# motor_module.net
KiCad netlist of a schematic drawn in EAGLE
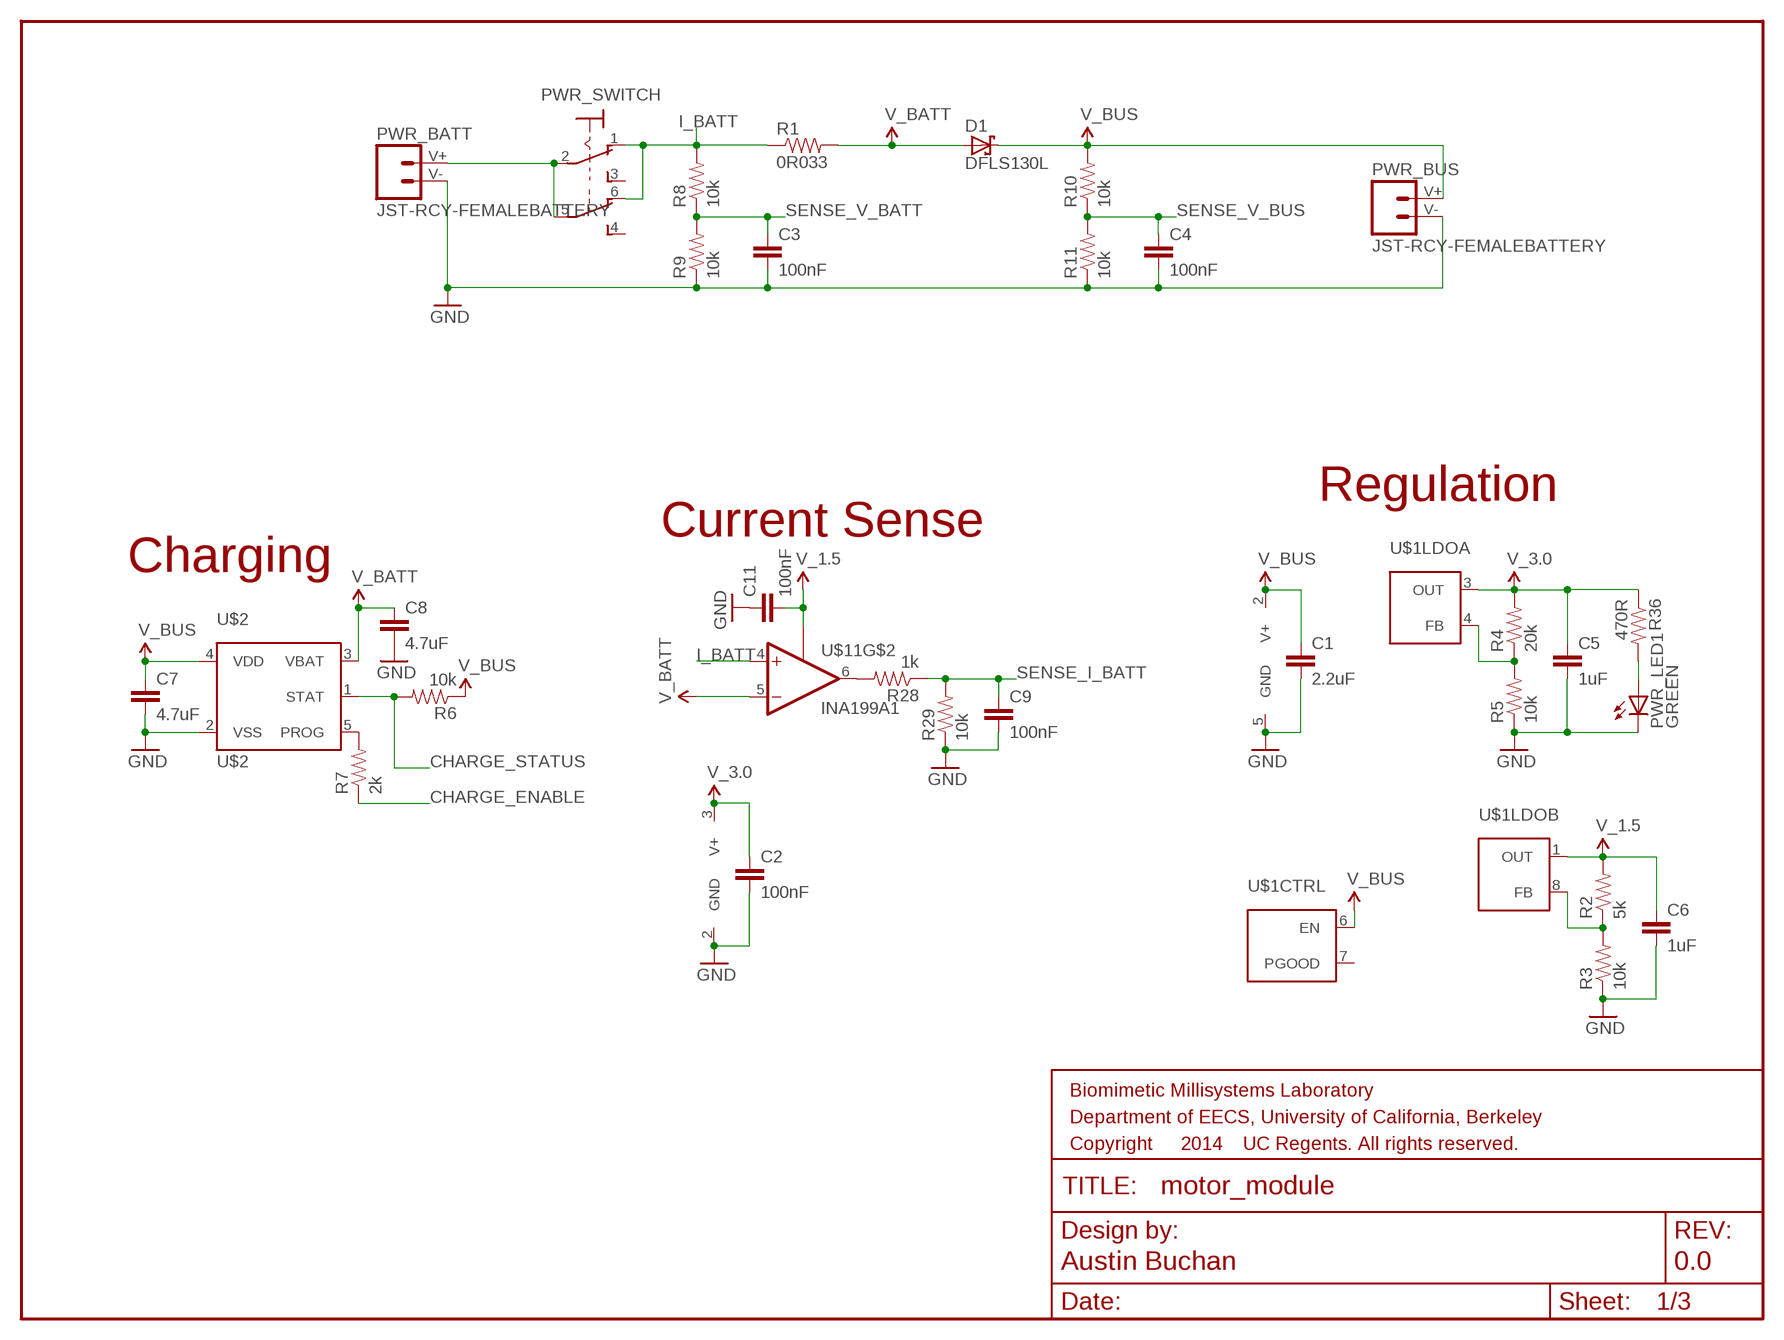
[diagram p0: schematic, sheet 1]
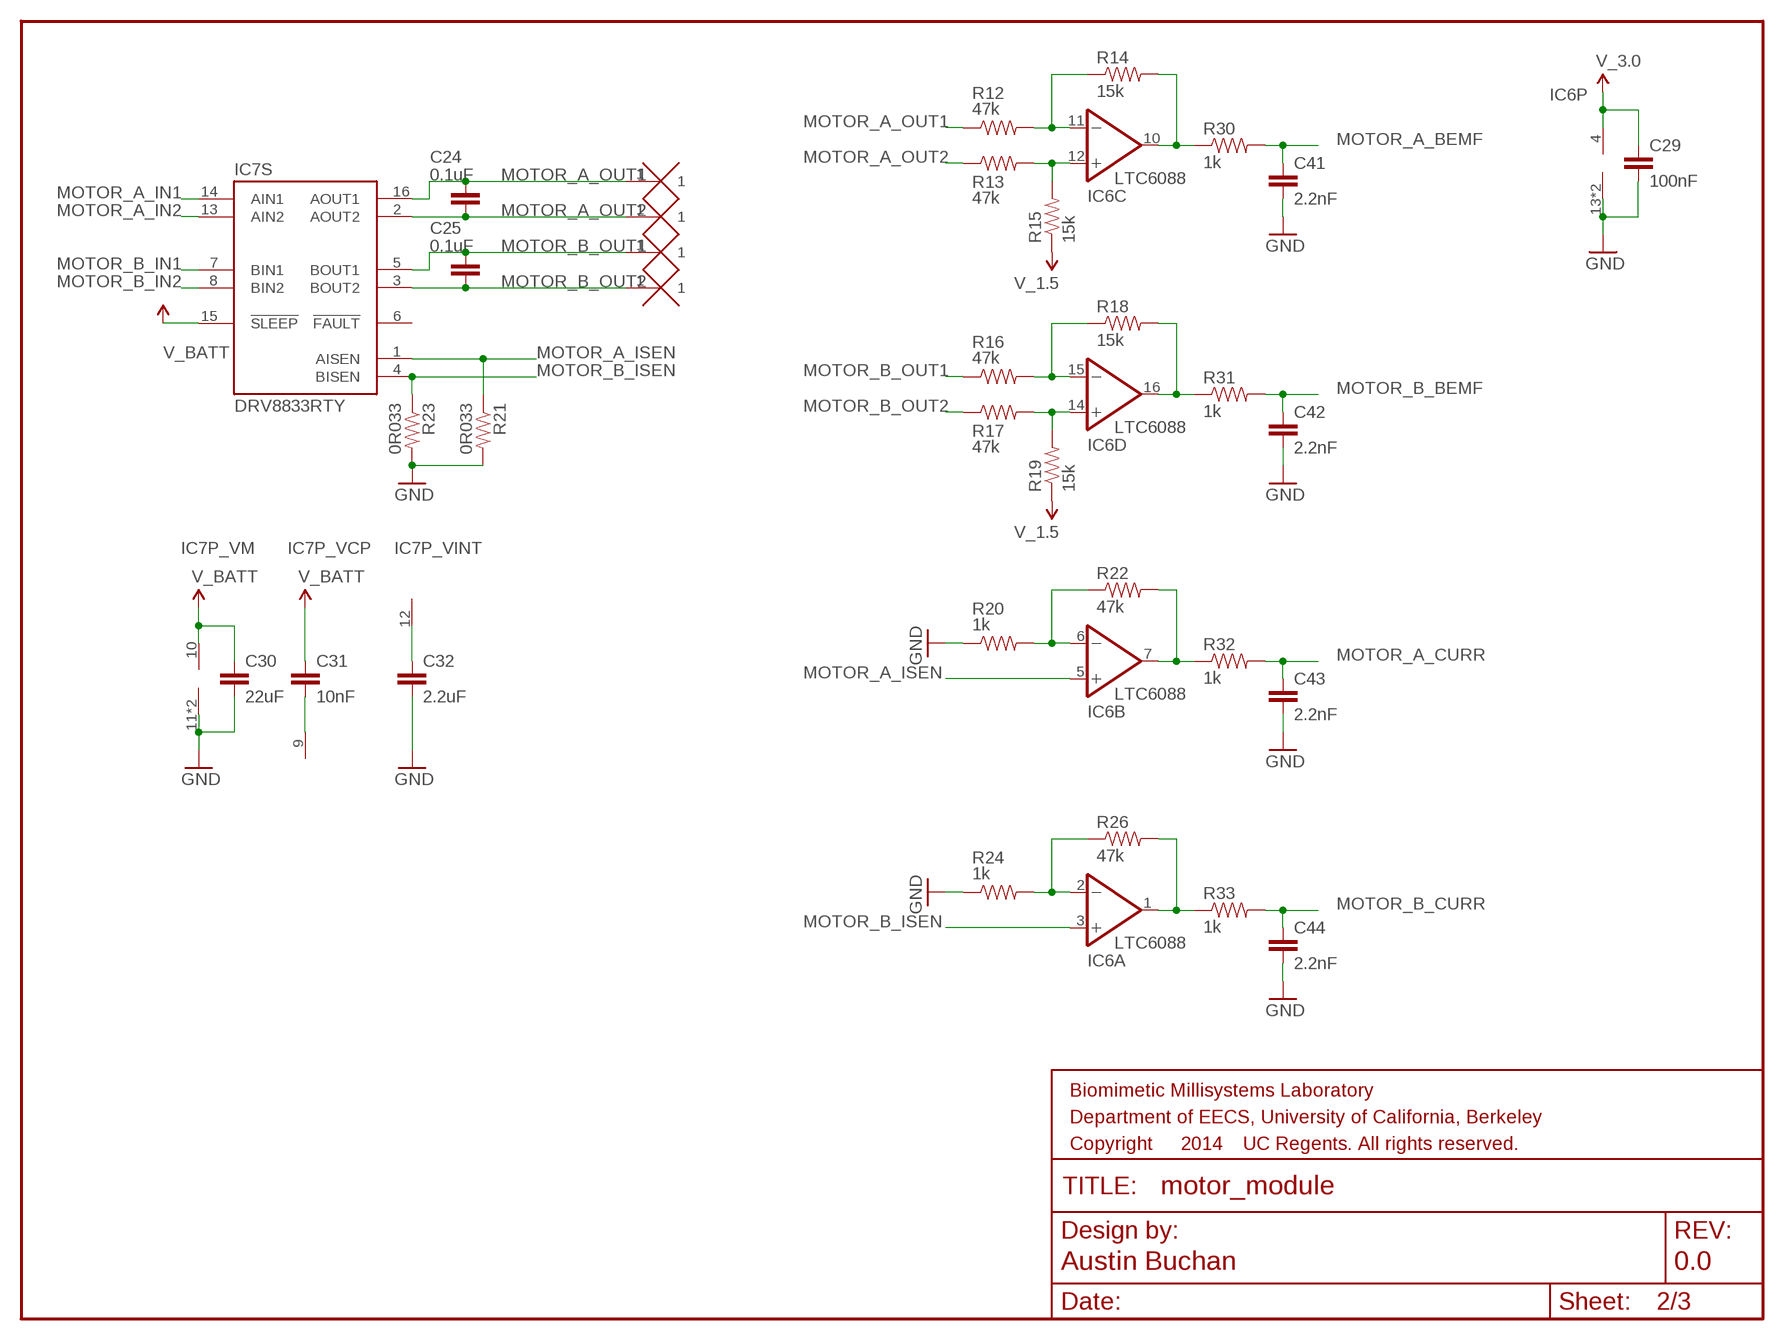
[diagram p1: schematic, sheet 2]
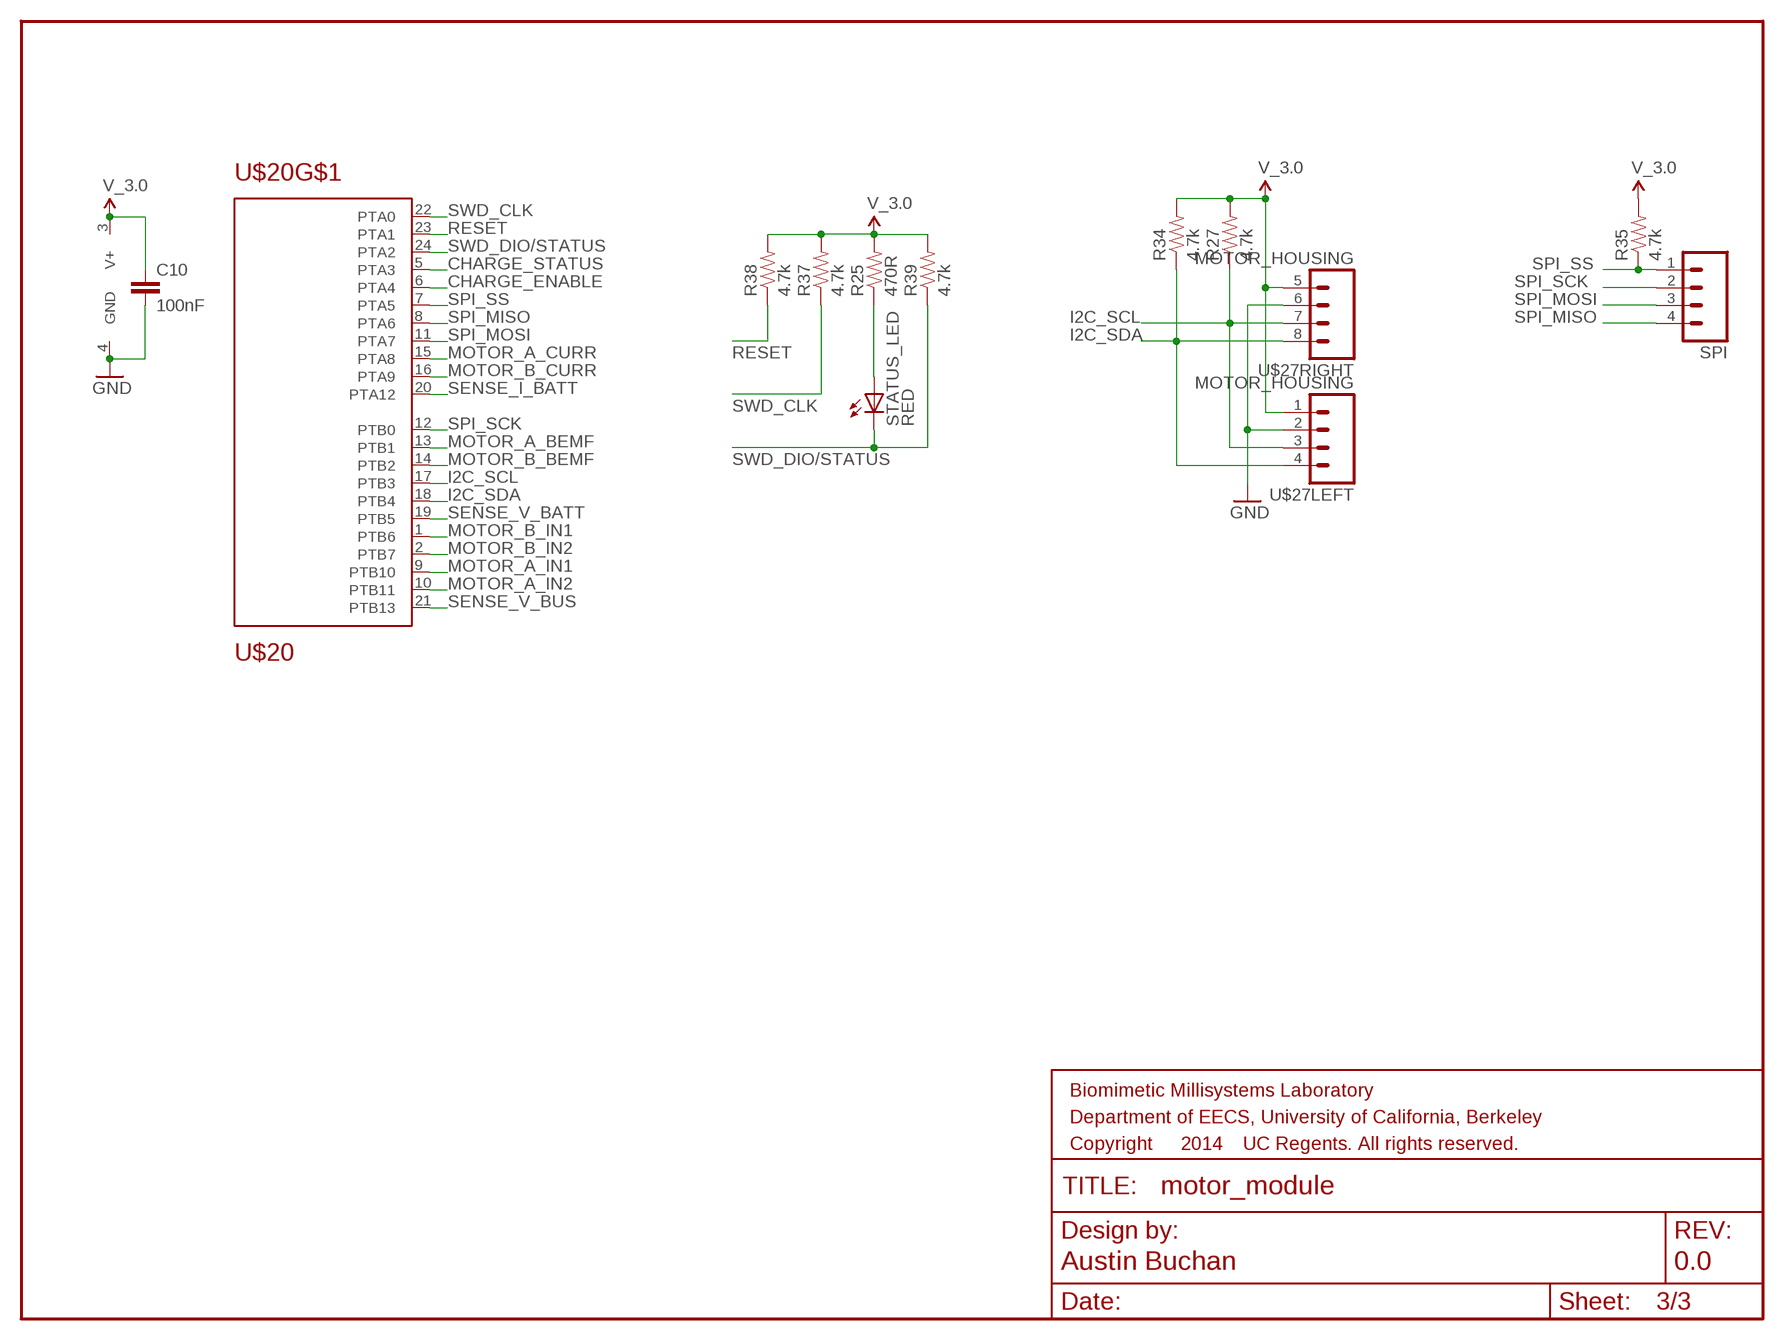
[diagram p2: schematic, sheet 3]

(export (version "E")
  (design (tool "Eeschema 10.0.6"))
  (components
    (comp (ref "C24")
      (value "0.1uF")
      (footprint "eagle-import:0402-CAP")
      (fields (field (name "VOLTAGE") "10V"))
      (libsource (lib "eagle-import") (part "CAP0402-CAP"))
    )
    (comp (ref "C25")
      (value "0.1uF")
      (footprint "eagle-import:0402-CAP")
      (fields (field (name "VOLTAGE") "10V"))
      (libsource (lib "eagle-import") (part "CAP0402-CAP"))
    )
    (comp (ref "C29")
      (value "100nF")
      (footprint "eagle-import:0402-CAP")
      (libsource (lib "eagle-import") (part "CAP0402-CAP"))
    )
    (comp (ref "C30")
      (value "22uF")
      (footprint "eagle-import:0603-CAP")
      (libsource (lib "eagle-import") (part "CAP0603-CAP"))
    )
    (comp (ref "C31")
      (value "10nF")
      (footprint "eagle-import:0402-CAP")
      (fields (field (name "VOLTAGE") "16V"))
      (libsource (lib "eagle-import") (part "CAP0402-CAP"))
    )
    (comp (ref "C32")
      (value "2.2uF")
      (footprint "eagle-import:0402-CAP")
      (fields (field (name "VOLTAGE") "6.3V"))
      (libsource (lib "eagle-import") (part "CAP0402-CAP"))
    )
    (comp (ref "C41")
      (value "2.2nF")
      (footprint "eagle-import:0402-CAP")
      (libsource (lib "eagle-import") (part "CAP0402-CAP"))
    )
    (comp (ref "C42")
      (value "2.2nF")
      (footprint "eagle-import:0402-CAP")
      (libsource (lib "eagle-import") (part "CAP0402-CAP"))
    )
    (comp (ref "C43")
      (value "2.2nF")
      (footprint "eagle-import:0402-CAP")
      (libsource (lib "eagle-import") (part "CAP0402-CAP"))
    )
    (comp (ref "C44")
      (value "2.2nF")
      (footprint "eagle-import:0402-CAP")
      (libsource (lib "eagle-import") (part "CAP0402-CAP"))
    )
    (comp (ref "IC6")
      (value "LTC6088")
      (footprint "eagle-import:DFN-16")
      (libsource (lib "eagle-import") (part "LTC6088"))
    )
    (comp (ref "IC7")
      (value "DRV8833RTY")
      (footprint "eagle-import:S-PWQFN-N16")
      (libsource (lib "eagle-import") (part "DRV8833RTY"))
    )
    (comp (ref "MA1")
      (value "PAD-0.6_1.8")
      (footprint "eagle-import:PAD_0.6_1.8")
      (libsource (lib "eagle-import") (part "PAD-0.6_1.8"))
    )
    (comp (ref "MA2")
      (value "PAD-0.6_1.8")
      (footprint "eagle-import:PAD_0.6_1.8")
      (libsource (lib "eagle-import") (part "PAD-0.6_1.8"))
    )
    (comp (ref "MB1")
      (value "PAD-0.6_1.8")
      (footprint "eagle-import:PAD_0.6_1.8")
      (libsource (lib "eagle-import") (part "PAD-0.6_1.8"))
    )
    (comp (ref "MB2")
      (value "PAD-0.6_1.8")
      (footprint "eagle-import:PAD_0.6_1.8")
      (libsource (lib "eagle-import") (part "PAD-0.6_1.8"))
    )
    (comp (ref "R12")
      (value "47k")
      (footprint "eagle-import:0402-RES")
      (fields (field (name "TOLERANCE") "1%"))
      (libsource (lib "eagle-import") (part "RESISTOR0402-RES"))
    )
    (comp (ref "R13")
      (value "47k")
      (footprint "eagle-import:0402-RES")
      (fields (field (name "TOLERANCE") "1%"))
      (libsource (lib "eagle-import") (part "RESISTOR0402-RES"))
    )
    (comp (ref "R14")
      (value "15k")
      (footprint "eagle-import:0402-RES")
      (fields (field (name "TOLERANCE") "1%"))
      (libsource (lib "eagle-import") (part "RESISTOR0402-RES"))
    )
    (comp (ref "R15")
      (value "15k")
      (footprint "eagle-import:0402-RES")
      (fields (field (name "TOLERANCE") "1%"))
      (libsource (lib "eagle-import") (part "RESISTOR0402-RES"))
    )
    (comp (ref "R16")
      (value "47k")
      (footprint "eagle-import:0402-RES")
      (fields (field (name "TOLERANCE") "1%"))
      (libsource (lib "eagle-import") (part "RESISTOR0402-RES"))
    )
    (comp (ref "R17")
      (value "47k")
      (footprint "eagle-import:0402-RES")
      (fields (field (name "TOLERANCE") "1%"))
      (libsource (lib "eagle-import") (part "RESISTOR0402-RES"))
    )
    (comp (ref "R18")
      (value "15k")
      (footprint "eagle-import:0402-RES")
      (fields (field (name "TOLERANCE") "1%"))
      (libsource (lib "eagle-import") (part "RESISTOR0402-RES"))
    )
    (comp (ref "R19")
      (value "15k")
      (footprint "eagle-import:0402-RES")
      (fields (field (name "TOLERANCE") "1%"))
      (libsource (lib "eagle-import") (part "RESISTOR0402-RES"))
    )
    (comp (ref "R20")
      (value "1k")
      (footprint "eagle-import:0402-RES")
      (fields (field (name "TOLERANCE") "1%"))
      (libsource (lib "eagle-import") (part "RESISTOR0402-RES"))
    )
    (comp (ref "R21")
      (value "0R033")
      (footprint "eagle-import:0603-RES")
      (libsource (lib "eagle-import") (part "RESISTOR0603-RES"))
    )
    (comp (ref "R22")
      (value "47k")
      (footprint "eagle-import:0402-RES")
      (fields (field (name "TOLERANCE") "1%"))
      (libsource (lib "eagle-import") (part "RESISTOR0402-RES"))
    )
    (comp (ref "R23")
      (value "0R033")
      (footprint "eagle-import:0603-RES")
      (libsource (lib "eagle-import") (part "RESISTOR0603-RES"))
    )
    (comp (ref "R24")
      (value "1k")
      (footprint "eagle-import:0402-RES")
      (fields (field (name "TOLERANCE") "1%"))
      (libsource (lib "eagle-import") (part "RESISTOR0402-RES"))
    )
    (comp (ref "R26")
      (value "47k")
      (footprint "eagle-import:0402-RES")
      (fields (field (name "TOLERANCE") "1%"))
      (libsource (lib "eagle-import") (part "RESISTOR0402-RES"))
    )
    (comp (ref "R30")
      (value "1k")
      (footprint "eagle-import:0402-RES")
      (libsource (lib "eagle-import") (part "RESISTOR0402-RES"))
    )
    (comp (ref "R31")
      (value "1k")
      (footprint "eagle-import:0402-RES")
      (libsource (lib "eagle-import") (part "RESISTOR0402-RES"))
    )
    (comp (ref "R32")
      (value "1k")
      (footprint "eagle-import:0402-RES")
      (libsource (lib "eagle-import") (part "RESISTOR0402-RES"))
    )
    (comp (ref "R33")
      (value "1k")
      (footprint "eagle-import:0402-RES")
      (libsource (lib "eagle-import") (part "RESISTOR0402-RES"))
    )
    (comp (ref "C1")
      (value "2.2uF")
      (footprint "eagle-import:0402-CAP")
      (libsource (lib "eagle-import") (part "CAP0402-CAP"))
    )
    (comp (ref "C2")
      (value "100nF")
      (footprint "eagle-import:0402-CAP")
      (libsource (lib "eagle-import") (part "CAP0402-CAP"))
    )
    (comp (ref "C3")
      (value "100nF")
      (footprint "eagle-import:0402-CAP")
      (libsource (lib "eagle-import") (part "CAP0402-CAP"))
    )
    (comp (ref "C4")
      (value "100nF")
      (footprint "eagle-import:0402-CAP")
      (libsource (lib "eagle-import") (part "CAP0402-CAP"))
    )
    (comp (ref "C5")
      (value "1uF")
      (footprint "eagle-import:0402-CAP")
      (libsource (lib "eagle-import") (part "CAP0402-CAP"))
    )
    (comp (ref "C6")
      (value "1uF")
      (footprint "eagle-import:0402-CAP")
      (libsource (lib "eagle-import") (part "CAP0402-CAP"))
    )
    (comp (ref "C7")
      (value "4.7uF")
      (footprint "eagle-import:0402-CAP")
      (libsource (lib "eagle-import") (part "CAP0402-CAP"))
    )
    (comp (ref "C8")
      (value "4.7uF")
      (footprint "eagle-import:0402-CAP")
      (libsource (lib "eagle-import") (part "CAP0402-CAP"))
    )
    (comp (ref "C9")
      (value "100nF")
      (footprint "eagle-import:0402-CAP")
      (libsource (lib "eagle-import") (part "CAP0402-CAP"))
    )
    (comp (ref "C11")
      (value "100nF")
      (footprint "eagle-import:0402-CAP")
      (libsource (lib "eagle-import") (part "CAP0402-CAP"))
    )
    (comp (ref "D1")
      (value "DFLS130L")
      (footprint "eagle-import:POWERDI123")
      (libsource (lib "eagle-import") (part "DFLS130L"))
    )
    (comp (ref "PWR_BATT")
      (value "JST-RCY-FEMALEBATTERY")
      (footprint "eagle-import:TP_LIPO_160MAH")
      (libsource (lib "eagle-import") (part "JST-RCY-FEMALEBATTERY"))
    )
    (comp (ref "PWR_BUS")
      (value "JST-RCY-FEMALEBATTERY")
      (footprint "eagle-import:TP_LIPO_160MAH")
      (libsource (lib "eagle-import") (part "JST-RCY-FEMALEBATTERY"))
    )
    (comp (ref "PWR_LED1")
      (value "GREEN")
      (footprint "eagle-import:LED-0603")
      (libsource (lib "eagle-import") (part "LED0603"))
    )
    (comp (ref "PWR_SWITCH")
      (value "JS202011SCQN")
      (footprint "eagle-import:JS202011SCQN")
      (libsource (lib "eagle-import") (part "JS202011SCQN"))
    )
    (comp (ref "R1")
      (value "0R033")
      (footprint "eagle-import:0603-RES")
      (libsource (lib "eagle-import") (part "RESISTOR0603-RES"))
    )
    (comp (ref "R2")
      (value "5k")
      (footprint "eagle-import:0402-RES")
      (libsource (lib "eagle-import") (part "RESISTOR0402-RES"))
    )
    (comp (ref "R3")
      (value "10k")
      (footprint "eagle-import:0402-RES")
      (libsource (lib "eagle-import") (part "RESISTOR0402-RES"))
    )
    (comp (ref "R4")
      (value "20k")
      (footprint "eagle-import:0402-RES")
      (libsource (lib "eagle-import") (part "RESISTOR0402-RES"))
    )
    (comp (ref "R5")
      (value "10k")
      (footprint "eagle-import:0402-RES")
      (libsource (lib "eagle-import") (part "RESISTOR0402-RES"))
    )
    (comp (ref "R6")
      (value "10k")
      (footprint "eagle-import:0402-RES")
      (libsource (lib "eagle-import") (part "RESISTOR0402-RES"))
    )
    (comp (ref "R7")
      (value "2k")
      (footprint "eagle-import:0402-RES")
      (libsource (lib "eagle-import") (part "RESISTOR0402-RES"))
    )
    (comp (ref "R8")
      (value "10k")
      (footprint "eagle-import:0402-RES")
      (libsource (lib "eagle-import") (part "RESISTOR0402-RES"))
    )
    (comp (ref "R9")
      (value "10k")
      (footprint "eagle-import:0402-RES")
      (libsource (lib "eagle-import") (part "RESISTOR0402-RES"))
    )
    (comp (ref "R10")
      (value "10k")
      (footprint "eagle-import:0402-RES")
      (libsource (lib "eagle-import") (part "RESISTOR0402-RES"))
    )
    (comp (ref "R11")
      (value "10k")
      (footprint "eagle-import:0402-RES")
      (libsource (lib "eagle-import") (part "RESISTOR0402-RES"))
    )
    (comp (ref "R28")
      (value "1k")
      (footprint "eagle-import:0402-RES")
      (libsource (lib "eagle-import") (part "RESISTOR0402-RES"))
    )
    (comp (ref "R29")
      (value "10k")
      (footprint "eagle-import:0402-RES")
      (libsource (lib "eagle-import") (part "RESISTOR0402-RES"))
    )
    (comp (ref "R36")
      (value "470R")
      (footprint "eagle-import:0402-RES")
      (libsource (lib "eagle-import") (part "RESISTOR0402-RES"))
    )
    (comp (ref "U$1")
      (value "SC560C")
      (footprint "eagle-import:MLPQ-UT8")
      (libsource (lib "eagle-import") (part "SC560C"))
    )
    (comp (ref "U$2")
      (value "MCP73831T")
      (footprint "eagle-import:SOT23-5")
      (libsource (lib "eagle-import") (part "MCP73831T"))
    )
    (comp (ref "U$11")
      (value "INA199A1")
      (footprint "eagle-import:SC70-6")
      (libsource (lib "eagle-import") (part "INA199A1"))
    )
    (comp (ref "C10")
      (value "100nF")
      (footprint "eagle-import:0402-CAP")
      (libsource (lib "eagle-import") (part "CAP0402-CAP"))
    )
    (comp (ref "R25")
      (value "470R")
      (footprint "eagle-import:0402-RES")
      (libsource (lib "eagle-import") (part "RESISTOR0402-RES"))
    )
    (comp (ref "R27")
      (value "4.7k")
      (footprint "eagle-import:0402-RES")
      (libsource (lib "eagle-import") (part "RESISTOR0402-RES"))
    )
    (comp (ref "R34")
      (value "4.7k")
      (footprint "eagle-import:0402-RES")
      (libsource (lib "eagle-import") (part "RESISTOR0402-RES"))
    )
    (comp (ref "R35")
      (value "4.7k")
      (footprint "eagle-import:0402-RES")
      (libsource (lib "eagle-import") (part "RESISTOR0402-RES"))
    )
    (comp (ref "R37")
      (value "4.7k")
      (footprint "eagle-import:0402-RES")
      (libsource (lib "eagle-import") (part "RESISTOR0402-RES"))
    )
    (comp (ref "R38")
      (value "4.7k")
      (footprint "eagle-import:0402-RES")
      (libsource (lib "eagle-import") (part "RESISTOR0402-RES"))
    )
    (comp (ref "R39")
      (value "4.7k")
      (footprint "eagle-import:0402-RES")
      (libsource (lib "eagle-import") (part "RESISTOR0402-RES"))
    )
    (comp (ref "SPI")
      (value "M04FFC")
      (footprint "eagle-import:MOLEX_503480-0400")
      (libsource (lib "eagle-import") (part "M04FFC"))
    )
    (comp (ref "STATUS_LED")
      (value "RED")
      (footprint "eagle-import:LED-0603")
      (libsource (lib "eagle-import") (part "LED0603"))
    )
    (comp (ref "U$20")
      (value "MKL05Z32VFK4")
      (footprint "eagle-import:QFN-24")
      (libsource (lib "eagle-import") (part "MKL05Z32VFK4"))
    )
    (comp (ref "U$27")
      (value "MOTOR_HOUSING")
      (footprint "eagle-import:MOTOR_HOUSING")
      (libsource (lib "eagle-import") (part "MOTOR_HOUSING"))
    )
  )
  (nets
    (net (code "1") (name "CHARGE_ENABLE") (class "Default")
      (node (ref "R7") (pin "1") (pinfunction "1_1") (pintype "passive"))
      (node (ref "U$20") (pin "6") (pinfunction "PTA4_6") (pintype "bidirectional"))
    )
    (net (code "2") (name "CHARGE_STATUS") (class "Default")
      (node (ref "R6") (pin "2") (pinfunction "2_2") (pintype "passive"))
      (node (ref "U$2") (pin "1") (pinfunction "STAT_1") (pintype "bidirectional"))
      (node (ref "U$20") (pin "5") (pinfunction "PTA3_5") (pintype "bidirectional"))
    )
    (net (code "3") (name "GND") (class "Default")
      (node (ref "C1") (pin "2") (pinfunction "2_2") (pintype "passive"))
      (node (ref "C10") (pin "2") (pinfunction "2_2") (pintype "passive"))
      (node (ref "C11") (pin "1") (pinfunction "1_1") (pintype "passive"))
      (node (ref "C2") (pin "2") (pinfunction "2_2") (pintype "passive"))
      (node (ref "C29") (pin "2") (pinfunction "2_2") (pintype "passive"))
      (node (ref "C3") (pin "2") (pinfunction "2_2") (pintype "passive"))
      (node (ref "C30") (pin "2") (pinfunction "2_2") (pintype "passive"))
      (node (ref "C32") (pin "2") (pinfunction "2_2") (pintype "passive"))
      (node (ref "C4") (pin "2") (pinfunction "2_2") (pintype "passive"))
      (node (ref "C41") (pin "2") (pinfunction "2_2") (pintype "passive"))
      (node (ref "C42") (pin "2") (pinfunction "2_2") (pintype "passive"))
      (node (ref "C43") (pin "2") (pinfunction "2_2") (pintype "passive"))
      (node (ref "C44") (pin "2") (pinfunction "2_2") (pintype "passive"))
      (node (ref "C5") (pin "2") (pinfunction "2_2") (pintype "passive"))
      (node (ref "C6") (pin "2") (pinfunction "2_2") (pintype "passive"))
      (node (ref "C7") (pin "2") (pinfunction "2_2") (pintype "passive"))
      (node (ref "C8") (pin "2") (pinfunction "2_2") (pintype "passive"))
      (node (ref "C9") (pin "2") (pinfunction "2_2") (pintype "passive"))
      (node (ref "IC6") (pin "13") (pinfunction "V-_13") (pintype "power_in"))
      (node (ref "IC6") (pin "PAD") (pinfunction "V-_PAD") (pintype "power_in"))
      (node (ref "IC7") (pin "11") (pinfunction "V-_11") (pintype "power_in"))
      (node (ref "IC7") (pin "PPAD") (pinfunction "V-_PPAD") (pintype "power_in"))
      (node (ref "PWR_BATT") (pin "V-") (pinfunction "1_V-") (pintype "passive"))
      (node (ref "PWR_BUS") (pin "V-") (pinfunction "1_V-") (pintype "passive"))
      (node (ref "PWR_LED1") (pin "C") (pinfunction "C_C") (pintype "passive"))
      (node (ref "R11") (pin "1") (pinfunction "1_1") (pintype "passive"))
      (node (ref "R20") (pin "1") (pinfunction "1_1") (pintype "passive"))
      (node (ref "R21") (pin "2") (pinfunction "2_2") (pintype "passive"))
      (node (ref "R23") (pin "2") (pinfunction "2_2") (pintype "passive"))
      (node (ref "R24") (pin "1") (pinfunction "1_1") (pintype "passive"))
      (node (ref "R29") (pin "1") (pinfunction "1_1") (pintype "passive"))
      (node (ref "R3") (pin "1") (pinfunction "1_1") (pintype "passive"))
      (node (ref "R5") (pin "1") (pinfunction "1_1") (pintype "passive"))
      (node (ref "R9") (pin "1") (pinfunction "1_1") (pintype "passive"))
      (node (ref "U$1") (pin "5") (pinfunction "GND_5") (pintype "power_in"))
      (node (ref "U$11") (pin "2") (pinfunction "GND_2") (pintype "power_in"))
      (node (ref "U$2") (pin "2") (pinfunction "VSS_2") (pintype "bidirectional"))
      (node (ref "U$20") (pin "4") (pinfunction "GND_4") (pintype "power_in"))
      (node (ref "U$27") (pin "2") (pinfunction "2_2") (pintype "passive"))
      (node (ref "U$27") (pin "6") (pinfunction "2_6") (pintype "passive"))
    )
    (net (code "4") (name "I2C_SCL") (class "Default")
      (node (ref "R27") (pin "1") (pinfunction "1_1") (pintype "passive"))
      (node (ref "U$20") (pin "17") (pinfunction "PTB3_17") (pintype "bidirectional"))
      (node (ref "U$27") (pin "3") (pinfunction "3_3") (pintype "passive"))
      (node (ref "U$27") (pin "7") (pinfunction "3_7") (pintype "passive"))
    )
    (net (code "5") (name "I2C_SDA") (class "Default")
      (node (ref "R34") (pin "1") (pinfunction "1_1") (pintype "passive"))
      (node (ref "U$20") (pin "18") (pinfunction "PTB4_18") (pintype "bidirectional"))
      (node (ref "U$27") (pin "4") (pinfunction "4_4") (pintype "passive"))
      (node (ref "U$27") (pin "8") (pinfunction "4_8") (pintype "passive"))
    )
    (net (code "6") (name "I_BATT") (class "Default")
      (node (ref "PWR_SWITCH") (pin "1") (pinfunction "O_1") (pintype "passive"))
      (node (ref "PWR_SWITCH") (pin "6") (pinfunction "O_6") (pintype "passive"))
      (node (ref "R1") (pin "1") (pinfunction "1_1") (pintype "passive"))
      (node (ref "R8") (pin "2") (pinfunction "2_2") (pintype "passive"))
      (node (ref "U$11") (pin "4") (pinfunction "+IN_4") (pintype "input"))
    )
    (net (code "7") (name "MOTOR_A_BEMF") (class "Default")
      (node (ref "C41") (pin "1") (pinfunction "1_1") (pintype "passive"))
      (node (ref "R30") (pin "2") (pinfunction "2_2") (pintype "passive"))
      (node (ref "U$20") (pin "13") (pinfunction "PTB1_13") (pintype "bidirectional"))
    )
    (net (code "8") (name "MOTOR_A_CURR") (class "Default")
      (node (ref "C43") (pin "1") (pinfunction "1_1") (pintype "passive"))
      (node (ref "R32") (pin "2") (pinfunction "2_2") (pintype "passive"))
      (node (ref "U$20") (pin "15") (pinfunction "PTA8_15") (pintype "bidirectional"))
    )
    (net (code "9") (name "MOTOR_A_IN1") (class "Default")
      (node (ref "IC7") (pin "14") (pinfunction "AIN1_14") (pintype "bidirectional"))
      (node (ref "U$20") (pin "9") (pinfunction "PTB10_9") (pintype "bidirectional"))
    )
    (net (code "10") (name "MOTOR_A_IN2") (class "Default")
      (node (ref "IC7") (pin "13") (pinfunction "AIN2_13") (pintype "bidirectional"))
      (node (ref "U$20") (pin "10") (pinfunction "PTB11_10") (pintype "bidirectional"))
    )
    (net (code "11") (name "MOTOR_A_ISEN") (class "Default")
      (node (ref "IC6") (pin "5") (pinfunction "+IN_5") (pintype "input"))
      (node (ref "IC7") (pin "1") (pinfunction "AISEN_1") (pintype "bidirectional"))
      (node (ref "R21") (pin "1") (pinfunction "1_1") (pintype "passive"))
    )
    (net (code "12") (name "MOTOR_A_OUT1") (class "Default")
      (node (ref "C24") (pin "1") (pinfunction "1_1") (pintype "passive"))
      (node (ref "IC7") (pin "16") (pinfunction "AOUT1_16") (pintype "bidirectional"))
      (node (ref "MA1") (pin "1") (pinfunction "1_1") (pintype "bidirectional"))
      (node (ref "R12") (pin "1") (pinfunction "1_1") (pintype "passive"))
    )
    (net (code "13") (name "MOTOR_A_OUT2") (class "Default")
      (node (ref "C24") (pin "2") (pinfunction "2_2") (pintype "passive"))
      (node (ref "IC7") (pin "2") (pinfunction "AOUT2_2") (pintype "bidirectional"))
      (node (ref "MA2") (pin "1") (pinfunction "1_1") (pintype "bidirectional"))
      (node (ref "R13") (pin "1") (pinfunction "1_1") (pintype "passive"))
    )
    (net (code "14") (name "MOTOR_B_BEMF") (class "Default")
      (node (ref "C42") (pin "1") (pinfunction "1_1") (pintype "passive"))
      (node (ref "R31") (pin "2") (pinfunction "2_2") (pintype "passive"))
      (node (ref "U$20") (pin "14") (pinfunction "PTB2_14") (pintype "bidirectional"))
    )
    (net (code "15") (name "MOTOR_B_CURR") (class "Default")
      (node (ref "C44") (pin "1") (pinfunction "1_1") (pintype "passive"))
      (node (ref "R33") (pin "2") (pinfunction "2_2") (pintype "passive"))
      (node (ref "U$20") (pin "16") (pinfunction "PTA9_16") (pintype "bidirectional"))
    )
    (net (code "16") (name "MOTOR_B_IN1") (class "Default")
      (node (ref "IC7") (pin "7") (pinfunction "BIN1_7") (pintype "bidirectional"))
      (node (ref "U$20") (pin "1") (pinfunction "PTB6_1") (pintype "bidirectional"))
    )
    (net (code "17") (name "MOTOR_B_IN2") (class "Default")
      (node (ref "IC7") (pin "8") (pinfunction "BIN2_8") (pintype "bidirectional"))
      (node (ref "U$20") (pin "2") (pinfunction "PTB7_2") (pintype "bidirectional"))
    )
    (net (code "18") (name "MOTOR_B_ISEN") (class "Default")
      (node (ref "IC6") (pin "3") (pinfunction "+IN_3") (pintype "input"))
      (node (ref "IC7") (pin "4") (pinfunction "BISEN_4") (pintype "bidirectional"))
      (node (ref "R23") (pin "1") (pinfunction "1_1") (pintype "passive"))
    )
    (net (code "19") (name "MOTOR_B_OUT1") (class "Default")
      (node (ref "C25") (pin "1") (pinfunction "1_1") (pintype "passive"))
      (node (ref "IC7") (pin "5") (pinfunction "BOUT1_5") (pintype "bidirectional"))
      (node (ref "MB1") (pin "1") (pinfunction "1_1") (pintype "bidirectional"))
      (node (ref "R16") (pin "1") (pinfunction "1_1") (pintype "passive"))
    )
    (net (code "20") (name "MOTOR_B_OUT2") (class "Default")
      (node (ref "C25") (pin "2") (pinfunction "2_2") (pintype "passive"))
      (node (ref "IC7") (pin "3") (pinfunction "BOUT2_3") (pintype "bidirectional"))
      (node (ref "MB2") (pin "1") (pinfunction "1_1") (pintype "bidirectional"))
      (node (ref "R17") (pin "1") (pinfunction "1_1") (pintype "passive"))
    )
    (net (code "21") (name "Net-(IC6A--IN)") (class "Default")
      (node (ref "IC6") (pin "2") (pinfunction "-IN_2") (pintype "input"))
      (node (ref "R24") (pin "2") (pinfunction "2_2") (pintype "passive"))
      (node (ref "R26") (pin "1") (pinfunction "1_1") (pintype "passive"))
    )
    (net (code "22") (name "Net-(IC6A-OUT)") (class "Default")
      (node (ref "IC6") (pin "1") (pinfunction "OUT_1") (pintype "output"))
      (node (ref "R26") (pin "2") (pinfunction "2_2") (pintype "passive"))
      (node (ref "R33") (pin "1") (pinfunction "1_1") (pintype "passive"))
    )
    (net (code "23") (name "Net-(IC6B--IN)") (class "Default")
      (node (ref "IC6") (pin "6") (pinfunction "-IN_6") (pintype "input"))
      (node (ref "R20") (pin "2") (pinfunction "2_2") (pintype "passive"))
      (node (ref "R22") (pin "1") (pinfunction "1_1") (pintype "passive"))
    )
    (net (code "24") (name "Net-(IC6B-OUT)") (class "Default")
      (node (ref "IC6") (pin "7") (pinfunction "OUT_7") (pintype "output"))
      (node (ref "R22") (pin "2") (pinfunction "2_2") (pintype "passive"))
      (node (ref "R32") (pin "1") (pinfunction "1_1") (pintype "passive"))
    )
    (net (code "25") (name "Net-(IC6C-+IN)") (class "Default")
      (node (ref "IC6") (pin "12") (pinfunction "+IN_12") (pintype "input"))
      (node (ref "R13") (pin "2") (pinfunction "2_2") (pintype "passive"))
      (node (ref "R15") (pin "2") (pinfunction "2_2") (pintype "passive"))
    )
    (net (code "26") (name "Net-(IC6C--IN)") (class "Default")
      (node (ref "IC6") (pin "11") (pinfunction "-IN_11") (pintype "input"))
      (node (ref "R12") (pin "2") (pinfunction "2_2") (pintype "passive"))
      (node (ref "R14") (pin "1") (pinfunction "1_1") (pintype "passive"))
    )
    (net (code "27") (name "Net-(IC6C-OUT)") (class "Default")
      (node (ref "IC6") (pin "10") (pinfunction "OUT_10") (pintype "output"))
      (node (ref "R14") (pin "2") (pinfunction "2_2") (pintype "passive"))
      (node (ref "R30") (pin "1") (pinfunction "1_1") (pintype "passive"))
    )
    (net (code "28") (name "Net-(IC6D-+IN)") (class "Default")
      (node (ref "IC6") (pin "14") (pinfunction "+IN_14") (pintype "input"))
      (node (ref "R17") (pin "2") (pinfunction "2_2") (pintype "passive"))
      (node (ref "R19") (pin "2") (pinfunction "2_2") (pintype "passive"))
    )
    (net (code "29") (name "Net-(IC6D--IN)") (class "Default")
      (node (ref "IC6") (pin "15") (pinfunction "-IN_15") (pintype "input"))
      (node (ref "R16") (pin "2") (pinfunction "2_2") (pintype "passive"))
      (node (ref "R18") (pin "1") (pinfunction "1_1") (pintype "passive"))
    )
    (net (code "30") (name "Net-(IC6D-OUT)") (class "Default")
      (node (ref "IC6") (pin "16") (pinfunction "OUT_16") (pintype "output"))
      (node (ref "R18") (pin "2") (pinfunction "2_2") (pintype "passive"))
      (node (ref "R31") (pin "1") (pinfunction "1_1") (pintype "passive"))
    )
    (net (code "31") (name "Net-(IC7A-V+)") (class "Default")
      (node (ref "C31") (pin "2") (pinfunction "2_2") (pintype "passive"))
      (node (ref "IC7") (pin "9") (pinfunction "V+_9") (pintype "power_in"))
    )
    (net (code "32") (name "Net-(IC7B-V-)") (class "Default")
      (node (ref "C32") (pin "1") (pinfunction "1_1") (pintype "passive"))
      (node (ref "IC7") (pin "12") (pinfunction "V-_12") (pintype "power_in"))
    )
    (net (code "33") (name "Net-(PWR_BATT-2)") (class "Default")
      (node (ref "PWR_BATT") (pin "V+") (pinfunction "2_V+") (pintype "passive"))
      (node (ref "PWR_SWITCH") (pin "2") (pinfunction "P_2") (pintype "passive"))
      (node (ref "PWR_SWITCH") (pin "5") (pinfunction "P_5") (pintype "passive"))
    )
    (net (code "34") (name "Net-(PWR_LED1-PadA)") (class "Default")
      (node (ref "PWR_LED1") (pin "A") (pinfunction "A_A") (pintype "passive"))
      (node (ref "R36") (pin "2") (pinfunction "2_2") (pintype "passive"))
    )
    (net (code "35") (name "Net-(R25-Pad1)") (class "Default")
      (node (ref "R25") (pin "1") (pinfunction "1_1") (pintype "passive"))
      (node (ref "STATUS_LED") (pin "A") (pinfunction "A_A") (pintype "passive"))
    )
    (net (code "36") (name "Net-(U$1C-FB)") (class "Default")
      (node (ref "R4") (pin "1") (pinfunction "1_1") (pintype "passive"))
      (node (ref "R5") (pin "2") (pinfunction "2_2") (pintype "passive"))
      (node (ref "U$1") (pin "4") (pinfunction "FB_4") (pintype "bidirectional"))
    )
    (net (code "37") (name "Net-(U$1D-FB)") (class "Default")
      (node (ref "R2") (pin "1") (pinfunction "1_1") (pintype "passive"))
      (node (ref "R3") (pin "2") (pinfunction "2_2") (pintype "passive"))
      (node (ref "U$1") (pin "8") (pinfunction "FB_8") (pintype "bidirectional"))
    )
    (net (code "38") (name "Net-(U$2-PROG)") (class "Default")
      (node (ref "R7") (pin "2") (pinfunction "2_2") (pintype "passive"))
      (node (ref "U$2") (pin "5") (pinfunction "PROG_5") (pintype "bidirectional"))
    )
    (net (code "39") (name "Net-(U$11B-OUT)") (class "Default")
      (node (ref "R28") (pin "2") (pinfunction "2_2") (pintype "passive"))
      (node (ref "U$11") (pin "6") (pinfunction "OUT_6") (pintype "output"))
    )
    (net (code "40") (name "RESET") (class "Default")
      (node (ref "R38") (pin "1") (pinfunction "1_1") (pintype "passive"))
      (node (ref "U$20") (pin "23") (pinfunction "PTA1_23") (pintype "bidirectional"))
    )
    (net (code "41") (name "SENSE_I_BATT") (class "Default")
      (node (ref "C9") (pin "1") (pinfunction "1_1") (pintype "passive"))
      (node (ref "R28") (pin "1") (pinfunction "1_1") (pintype "passive"))
      (node (ref "R29") (pin "2") (pinfunction "2_2") (pintype "passive"))
      (node (ref "U$20") (pin "20") (pinfunction "PTA12_20") (pintype "bidirectional"))
    )
    (net (code "42") (name "SENSE_V_BATT") (class "Default")
      (node (ref "C3") (pin "1") (pinfunction "1_1") (pintype "passive"))
      (node (ref "R8") (pin "1") (pinfunction "1_1") (pintype "passive"))
      (node (ref "R9") (pin "2") (pinfunction "2_2") (pintype "passive"))
      (node (ref "U$20") (pin "19") (pinfunction "PTB5_19") (pintype "bidirectional"))
    )
    (net (code "43") (name "SENSE_V_BUS") (class "Default")
      (node (ref "C4") (pin "1") (pinfunction "1_1") (pintype "passive"))
      (node (ref "R10") (pin "1") (pinfunction "1_1") (pintype "passive"))
      (node (ref "R11") (pin "2") (pinfunction "2_2") (pintype "passive"))
      (node (ref "U$20") (pin "21") (pinfunction "PTB13_21") (pintype "bidirectional"))
    )
    (net (code "44") (name "SPI_MISO") (class "Default")
      (node (ref "SPI") (pin "4") (pinfunction "4_4") (pintype "passive"))
      (node (ref "U$20") (pin "8") (pinfunction "PTA6_8") (pintype "bidirectional"))
    )
    (net (code "45") (name "SPI_MOSI") (class "Default")
      (node (ref "SPI") (pin "3") (pinfunction "3_3") (pintype "passive"))
      (node (ref "U$20") (pin "11") (pinfunction "PTA7_11") (pintype "bidirectional"))
    )
    (net (code "46") (name "SPI_SCK") (class "Default")
      (node (ref "SPI") (pin "2") (pinfunction "2_2") (pintype "passive"))
      (node (ref "U$20") (pin "12") (pinfunction "PTB0_12") (pintype "bidirectional"))
    )
    (net (code "47") (name "SPI_SS") (class "Default")
      (node (ref "R35") (pin "1") (pinfunction "1_1") (pintype "passive"))
      (node (ref "SPI") (pin "1") (pinfunction "1_1") (pintype "passive"))
      (node (ref "U$20") (pin "7") (pinfunction "PTA5_7") (pintype "bidirectional"))
    )
    (net (code "48") (name "SWD_CLK") (class "Default")
      (node (ref "R37") (pin "1") (pinfunction "1_1") (pintype "passive"))
      (node (ref "U$20") (pin "22") (pinfunction "PTA0_22") (pintype "bidirectional"))
    )
    (net (code "49") (name "SWD_DIO{slash}STATUS") (class "Default")
      (node (ref "R39") (pin "1") (pinfunction "1_1") (pintype "passive"))
      (node (ref "STATUS_LED") (pin "C") (pinfunction "C_C") (pintype "passive"))
      (node (ref "U$20") (pin "24") (pinfunction "PTA2_24") (pintype "bidirectional"))
    )
    (net (code "50") (name "V_1.5") (class "Default")
      (node (ref "C11") (pin "2") (pinfunction "2_2") (pintype "passive"))
      (node (ref "C6") (pin "1") (pinfunction "1_1") (pintype "passive"))
      (node (ref "R15") (pin "1") (pinfunction "1_1") (pintype "passive"))
      (node (ref "R19") (pin "1") (pinfunction "1_1") (pintype "passive"))
      (node (ref "R2") (pin "2") (pinfunction "2_2") (pintype "passive"))
      (node (ref "U$1") (pin "1") (pinfunction "OUT_1") (pintype "bidirectional"))
      (node (ref "U$11") (pin "1") (pinfunction "REF_1") (pintype "bidirectional"))
    )
    (net (code "51") (name "V_3.0") (class "Default")
      (node (ref "C10") (pin "1") (pinfunction "1_1") (pintype "passive"))
      (node (ref "C2") (pin "1") (pinfunction "1_1") (pintype "passive"))
      (node (ref "C29") (pin "1") (pinfunction "1_1") (pintype "passive"))
      (node (ref "C5") (pin "1") (pinfunction "1_1") (pintype "passive"))
      (node (ref "IC6") (pin "4") (pinfunction "V+_4") (pintype "power_in"))
      (node (ref "R25") (pin "2") (pinfunction "2_2") (pintype "passive"))
      (node (ref "R27") (pin "2") (pinfunction "2_2") (pintype "passive"))
      (node (ref "R34") (pin "2") (pinfunction "2_2") (pintype "passive"))
      (node (ref "R35") (pin "2") (pinfunction "2_2") (pintype "passive"))
      (node (ref "R36") (pin "1") (pinfunction "1_1") (pintype "passive"))
      (node (ref "R37") (pin "2") (pinfunction "2_2") (pintype "passive"))
      (node (ref "R38") (pin "2") (pinfunction "2_2") (pintype "passive"))
      (node (ref "R39") (pin "2") (pinfunction "2_2") (pintype "passive"))
      (node (ref "R4") (pin "2") (pinfunction "2_2") (pintype "passive"))
      (node (ref "U$1") (pin "3") (pinfunction "OUT_3") (pintype "bidirectional"))
      (node (ref "U$11") (pin "3") (pinfunction "V+_3") (pintype "power_in"))
      (node (ref "U$20") (pin "3") (pinfunction "V+_3") (pintype "power_in"))
      (node (ref "U$27") (pin "1") (pinfunction "1_1") (pintype "passive"))
      (node (ref "U$27") (pin "5") (pinfunction "1_5") (pintype "passive"))
    )
    (net (code "52") (name "V_BATT") (class "Default")
      (node (ref "C30") (pin "1") (pinfunction "1_1") (pintype "passive"))
      (node (ref "C31") (pin "1") (pinfunction "1_1") (pintype "passive"))
      (node (ref "C8") (pin "1") (pinfunction "1_1") (pintype "passive"))
      (node (ref "D1") (pin "A") (pinfunction "A_A") (pintype "passive"))
      (node (ref "IC7") (pin "10") (pinfunction "V+_10") (pintype "power_in"))
      (node (ref "IC7") (pin "15") (pinfunction "~{SLEEP}_15") (pintype "bidirectional"))
      (node (ref "R1") (pin "2") (pinfunction "2_2") (pintype "passive"))
      (node (ref "U$11") (pin "5") (pinfunction "-IN_5") (pintype "input"))
      (node (ref "U$2") (pin "3") (pinfunction "VBAT_3") (pintype "bidirectional"))
    )
    (net (code "53") (name "V_BUS") (class "Default")
      (node (ref "C1") (pin "1") (pinfunction "1_1") (pintype "passive"))
      (node (ref "C7") (pin "1") (pinfunction "1_1") (pintype "passive"))
      (node (ref "D1") (pin "C") (pinfunction "C_C") (pintype "passive"))
      (node (ref "PWR_BUS") (pin "V+") (pinfunction "2_V+") (pintype "passive"))
      (node (ref "R10") (pin "2") (pinfunction "2_2") (pintype "passive"))
      (node (ref "R6") (pin "1") (pinfunction "1_1") (pintype "passive"))
      (node (ref "U$1") (pin "2") (pinfunction "V+_2") (pintype "power_in"))
      (node (ref "U$1") (pin "6") (pinfunction "EN_6") (pintype "bidirectional"))
      (node (ref "U$2") (pin "4") (pinfunction "VDD_4") (pintype "bidirectional"))
    )
    (net (code "54") (name "unconnected-(IC7D-~{FAULT}-Pad6)") (class "Default")
      (node (ref "IC7") (pin "6") (pinfunction "~{FAULT}_6") (pintype "bidirectional"))
    )
    (net (code "55") (name "unconnected-(PWR_SWITCHA-S-Pad3)") (class "Default")
      (node (ref "PWR_SWITCH") (pin "3") (pinfunction "S_3") (pintype "passive"))
    )
    (net (code "56") (name "unconnected-(PWR_SWITCHB-S-Pad4)") (class "Default")
      (node (ref "PWR_SWITCH") (pin "4") (pinfunction "S_4") (pintype "passive"))
    )
    (net (code "57") (name "unconnected-(U$1A-PGOOD-Pad7)") (class "Default")
      (node (ref "U$1") (pin "7") (pinfunction "PGOOD_7") (pintype "bidirectional"))
    )
  )
)
